# Main_Circuit.net
KiCad netlist of a schematic drawn in Altium Designer
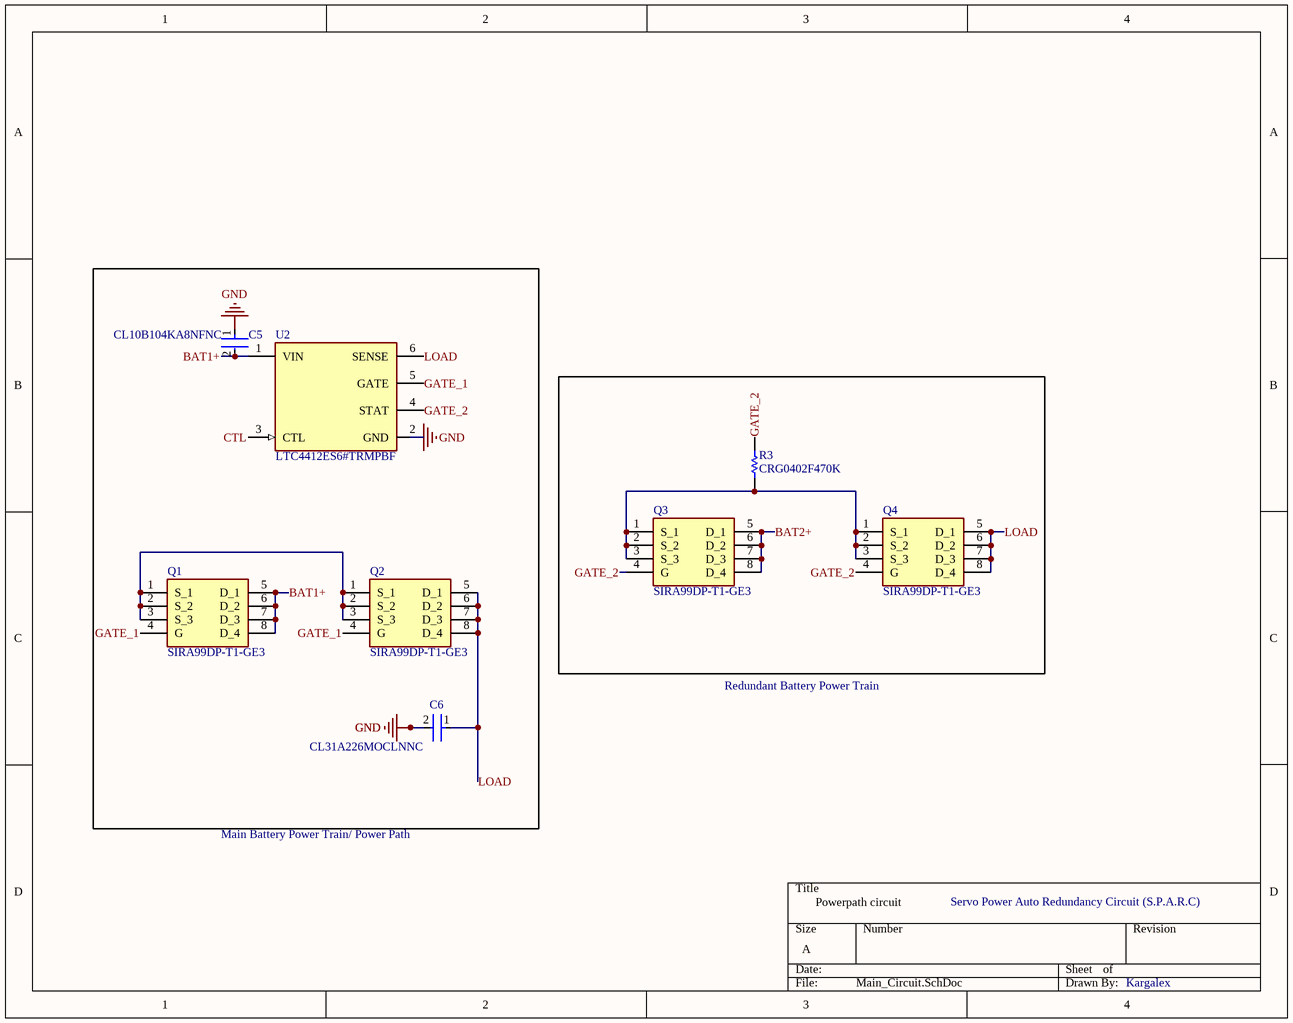
[diagram p0: Main_Circuit.SchDoc]

(export (version "E")
  (design (tool "Eeschema 10.0.6"))
  (components
    (comp (ref "C5")
      (value "CL10B104KA8NFNC")
      (footprint "FP-CL10-IPC_C")
      (description "Cap Ceramic 100nF 25V X7R ±10% Pad SMD 0603 +125°C T/R")
      (fields (field (name "TOLERANCE") "10%"))
      (libsource (lib "Altium Content Vault") (part "b4654b650e69147ec39a6b967a45e02"))
    )
    (comp (ref "C6")
      (value "CL31A226MOCLNNC")
      (footprint "FP-CL31-IPC_A")
      (description "Cap Ceramic 22uF 16V X5R ±20% SMD 1206 +85°C Embossed T/R")
      (fields (field (name "TOLERANCE") "20%") (field (name "VOLTAGE") "16V"))
      (libsource (lib "Altium Content Vault") (part "b4654b650e69147ec39a6b967a45e02"))
    )
    (comp (ref "Q1")
      (value "SIRA99DP-T1-GE3")
      (footprint "SamacSys:SI7141DPT1GE3")
      (description "MOSFET (P-Channel)")
      (fields (field (name "MOUSER PART NUMBER") "78-SIRA99DP-T1-GE3"))
      (libsource (lib "*") (part "SIRA99DP-T1-GE3"))
    )
    (comp (ref "Q2")
      (value "SIRA99DP-T1-GE3")
      (footprint "SamacSys:SI7141DPT1GE3")
      (description "MOSFET (P-Channel)")
      (fields (field (name "MOUSER PART NUMBER") "78-SIRA99DP-T1-GE3"))
      (libsource (lib "*") (part "SIRA99DP-T1-GE3"))
    )
    (comp (ref "Q3")
      (value "SIRA99DP-T1-GE3")
      (footprint "SamacSys:SI7141DPT1GE3")
      (description "MOSFET (P-Channel)")
      (fields (field (name "MOUSER PART NUMBER") "78-SIRA99DP-T1-GE3"))
      (libsource (lib "*") (part "SIRA99DP-T1-GE3"))
    )
    (comp (ref "Q4")
      (value "SIRA99DP-T1-GE3")
      (footprint "SamacSys:SI7141DPT1GE3")
      (description "MOSFET (P-Channel)")
      (fields (field (name "MOUSER PART NUMBER") "78-SIRA99DP-T1-GE3"))
      (libsource (lib "*") (part "SIRA99DP-T1-GE3"))
    )
    (comp (ref "R3")
      (value "CRG0402F470K")
      (footprint "RESC1005X40X25LL10T10")
      (fields (field (name "MANUFACTURER") "TE Connectivity / AMP"))
      (libsource (lib "Altium Content Vault") (part "RES"))
    )
    (comp (ref "U2")
      (value "LTC4412ES6#TRMPBF")
      (footprint "FP-S6-6-05-08-1636-IPC_C")
      (description "IC OR CTRLR SRC SELECT TSOT23-6")
      (libsource (lib "Altium Content Vault") (part "07cb0f4431a3a7488227ca1baae77bb"))
    )
  )
  (nets
    (net (code "1") (name "/BAT1+") (class "Default")
      (node (ref "C5") (pin "2") (pinfunction "2_2") (pintype "passive"))
      (node (ref "Q1") (pin "5") (pinfunction "D_1_5") (pintype "passive"))
      (node (ref "Q1") (pin "6") (pinfunction "D_2_6") (pintype "passive"))
      (node (ref "Q1") (pin "7") (pinfunction "D_3_7") (pintype "passive"))
      (node (ref "Q1") (pin "8") (pinfunction "D_4_8") (pintype "passive"))
      (node (ref "U2") (pin "1") (pinfunction "VIN_1") (pintype "power_in"))
    )
    (net (code "2") (name "/BAT2+") (class "Default")
      (node (ref "Q3") (pin "5") (pinfunction "D_1_5") (pintype "passive"))
      (node (ref "Q3") (pin "6") (pinfunction "D_2_6") (pintype "passive"))
      (node (ref "Q3") (pin "7") (pinfunction "D_3_7") (pintype "passive"))
      (node (ref "Q3") (pin "8") (pinfunction "D_4_8") (pintype "passive"))
    )
    (net (code "3") (name "/CTL") (class "Default")
      (node (ref "U2") (pin "3") (pinfunction "CTL_3") (pintype "input"))
    )
    (net (code "4") (name "/GATE_1") (class "Default")
      (node (ref "Q1") (pin "4") (pinfunction "G_4") (pintype "passive"))
      (node (ref "Q2") (pin "4") (pinfunction "G_4") (pintype "passive"))
      (node (ref "U2") (pin "5") (pinfunction "GATE_5") (pintype "passive"))
    )
    (net (code "5") (name "/GATE_2") (class "Default")
      (node (ref "Q3") (pin "4") (pinfunction "G_4") (pintype "passive"))
      (node (ref "Q4") (pin "4") (pinfunction "G_4") (pintype "passive"))
      (node (ref "R3") (pin "2") (pinfunction "2_2") (pintype "passive"))
      (node (ref "U2") (pin "4") (pinfunction "STAT_4") (pintype "open_collector"))
    )
    (net (code "6") (name "/LOAD") (class "Default")
      (node (ref "C6") (pin "1") (pinfunction "1_1") (pintype "passive"))
      (node (ref "Q2") (pin "5") (pinfunction "D_1_5") (pintype "passive"))
      (node (ref "Q2") (pin "6") (pinfunction "D_2_6") (pintype "passive"))
      (node (ref "Q2") (pin "7") (pinfunction "D_3_7") (pintype "passive"))
      (node (ref "Q2") (pin "8") (pinfunction "D_4_8") (pintype "passive"))
      (node (ref "Q4") (pin "5") (pinfunction "D_1_5") (pintype "passive"))
      (node (ref "Q4") (pin "6") (pinfunction "D_2_6") (pintype "passive"))
      (node (ref "Q4") (pin "7") (pinfunction "D_3_7") (pintype "passive"))
      (node (ref "Q4") (pin "8") (pinfunction "D_4_8") (pintype "passive"))
      (node (ref "U2") (pin "6") (pinfunction "SENSE_6") (pintype "passive"))
    )
    (net (code "7") (name "GND") (class "Default")
      (node (ref "C5") (pin "1") (pinfunction "1_1") (pintype "passive"))
      (node (ref "C6") (pin "2") (pinfunction "2_2") (pintype "passive"))
      (node (ref "U2") (pin "2") (pinfunction "GND_2") (pintype "power_in"))
    )
    (net (code "8") (name "Net-(Q1-S_1)") (class "Default")
      (node (ref "Q1") (pin "1") (pinfunction "S_1_1") (pintype "passive"))
      (node (ref "Q1") (pin "2") (pinfunction "S_2_2") (pintype "passive"))
      (node (ref "Q1") (pin "3") (pinfunction "S_3_3") (pintype "passive"))
      (node (ref "Q2") (pin "1") (pinfunction "S_1_1") (pintype "passive"))
      (node (ref "Q2") (pin "2") (pinfunction "S_2_2") (pintype "passive"))
      (node (ref "Q2") (pin "3") (pinfunction "S_3_3") (pintype "passive"))
    )
    (net (code "9") (name "Net-(Q3-S_1)") (class "Default")
      (node (ref "Q3") (pin "1") (pinfunction "S_1_1") (pintype "passive"))
      (node (ref "Q3") (pin "2") (pinfunction "S_2_2") (pintype "passive"))
      (node (ref "Q3") (pin "3") (pinfunction "S_3_3") (pintype "passive"))
      (node (ref "Q4") (pin "1") (pinfunction "S_1_1") (pintype "passive"))
      (node (ref "Q4") (pin "2") (pinfunction "S_2_2") (pintype "passive"))
      (node (ref "Q4") (pin "3") (pinfunction "S_3_3") (pintype "passive"))
      (node (ref "R3") (pin "1") (pinfunction "1_1") (pintype "passive"))
    )
  )
)
